# MCU.net
KiCad netlist of a schematic drawn in Altium Designer
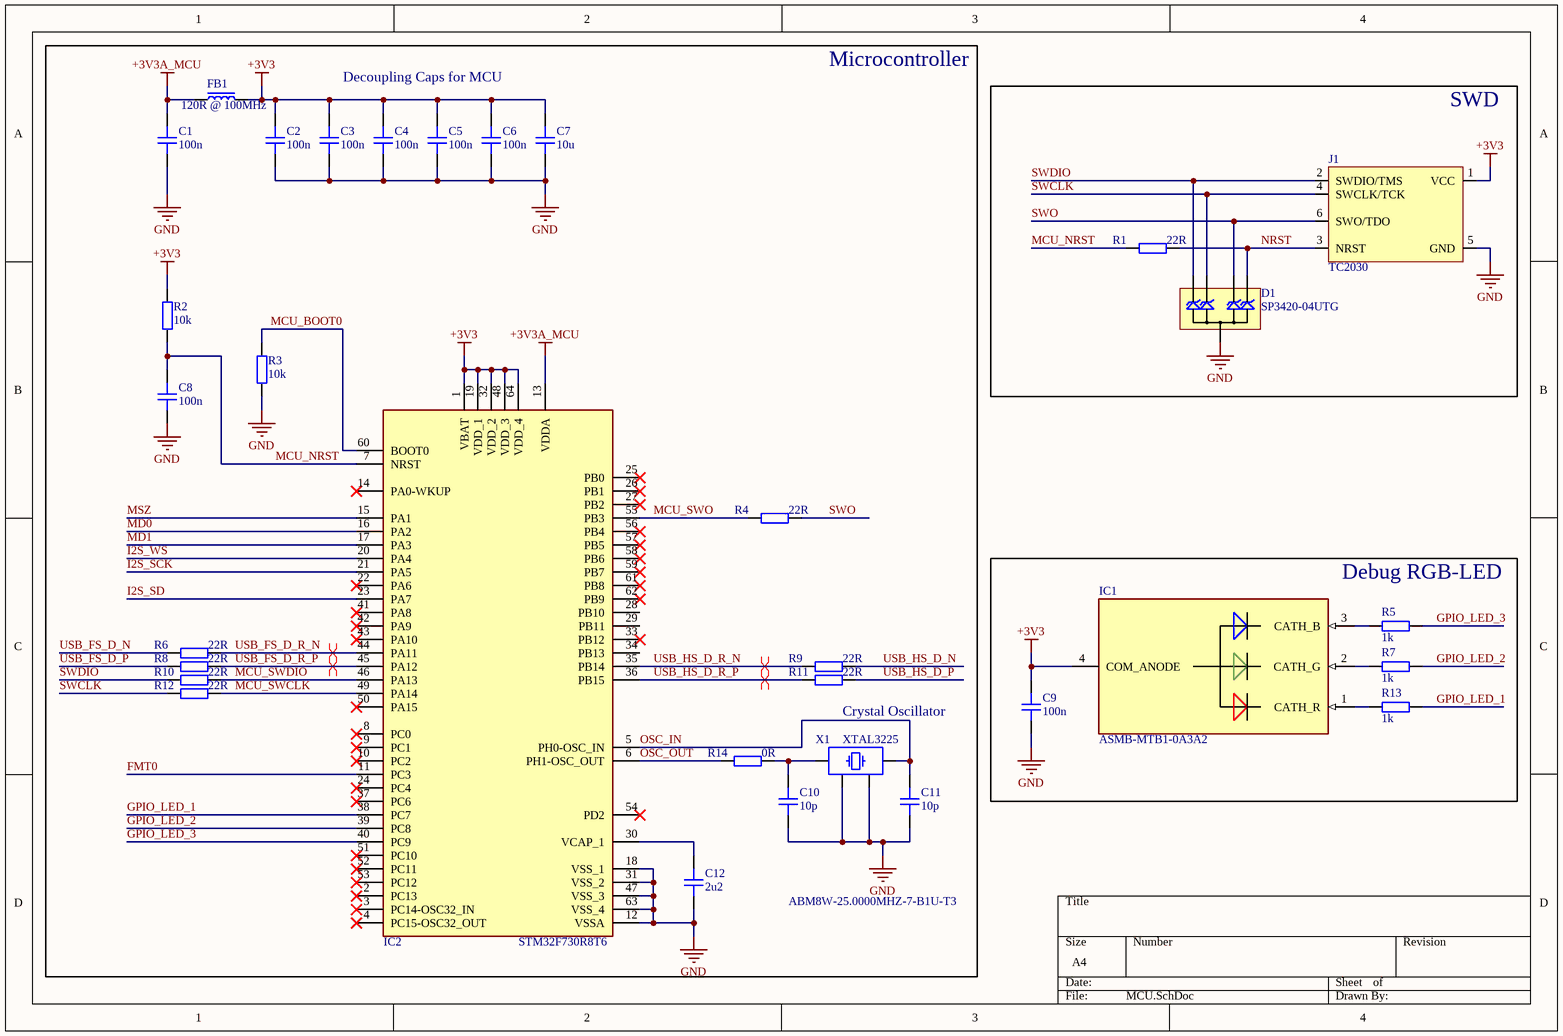
[diagram p0: MCU.SchDoc]

(export (version "E")
  (design (tool "Eeschema 10.0.6"))
  (components
    (comp (ref "C1")
      (value "100n")
      (footprint "CAP_0402")
      (description "Capacitor SMD 0402")
      (libsource (lib "Schematic-Lib-PhilsLab") (part "CAP_0402"))
    )
    (comp (ref "C2")
      (value "100n")
      (footprint "CAP_0402")
      (description "Capacitor SMD 0402")
      (libsource (lib "Schematic-Lib-PhilsLab") (part "CAP_0402"))
    )
    (comp (ref "C3")
      (value "100n")
      (footprint "CAP_0402")
      (description "Capacitor SMD 0402")
      (libsource (lib "Schematic-Lib-PhilsLab") (part "CAP_0402"))
    )
    (comp (ref "C4")
      (value "100n")
      (footprint "CAP_0402")
      (description "Capacitor SMD 0402")
      (libsource (lib "Schematic-Lib-PhilsLab") (part "CAP_0402"))
    )
    (comp (ref "C5")
      (value "100n")
      (footprint "CAP_0402")
      (description "Capacitor SMD 0402")
      (libsource (lib "Schematic-Lib-PhilsLab") (part "CAP_0402"))
    )
    (comp (ref "C6")
      (value "100n")
      (footprint "CAP_0402")
      (description "Capacitor SMD 0402")
      (libsource (lib "Schematic-Lib-PhilsLab") (part "CAP_0402"))
    )
    (comp (ref "C7")
      (value "10u")
      (footprint "CAP_0603")
      (description "Capacitor SMD 0603")
      (libsource (lib "Schematic-Lib-PhilsLab") (part "CAP_0603"))
    )
    (comp (ref "C8")
      (value "100n")
      (footprint "CAP_0402")
      (description "Capacitor SMD 0402")
      (libsource (lib "Schematic-Lib-PhilsLab") (part "CAP_0402"))
    )
    (comp (ref "C9")
      (value "100n")
      (footprint "CAP_0402")
      (description "Capacitor SMD 0402")
      (libsource (lib "Schematic-Lib-PhilsLab") (part "CAP_0402"))
    )
    (comp (ref "C10")
      (value "10p")
      (footprint "CAP_0402")
      (description "Capacitor SMD 0402")
      (libsource (lib "Schematic-Lib-PhilsLab") (part "CAP_0402"))
    )
    (comp (ref "C11")
      (value "10p")
      (footprint "CAP_0402")
      (description "Capacitor SMD 0402")
      (libsource (lib "Schematic-Lib-PhilsLab") (part "CAP_0402"))
    )
    (comp (ref "C12")
      (value "2u2")
      (footprint "CAP_0402")
      (description "Capacitor SMD 0402")
      (libsource (lib "Schematic-Lib-PhilsLab") (part "CAP_0402"))
    )
    (comp (ref "D1")
      (value "SP3420-04UTG")
      (footprint "uDFN-10")
      (description "TVS Diode Array Low Capacitance ESD Protection 4-Channel (Vwork=3V3, Vclamp=6V)")
      (fields (field (name "MANUFACTURER") "Littelfuse"))
      (libsource (lib "Schematic-Lib-PhilsLab") (part "SP3420-04UTG"))
    )
    (comp (ref "FB1")
      (value "120R @ 100MHz")
      (footprint "FB_0402")
      (description "Ferrite Bead SMD 0402")
      (libsource (lib "Schematic-Lib-PhilsLab") (part "FB_0402"))
    )
    (comp (ref "IC1")
      (value "ASMB-MTB1-0A3A2")
      (footprint "BAT_Detector_PCBLib:AVAGO_PLCC4")
      (description "Integrated Circuit")
      (fields (field (name "MOUSER PART NUMBER") "630-ASMB-MTB1-0A3A2"))
      (libsource (lib "BAT_Detector_SCHLib") (part "ASMB-MTB1-0A3A2"))
    )
    (comp (ref "IC2")
      (value "STM32F730R8T6")
      (footprint "BAT_Detector_PCBLib:QFP50P1200X1200X160-64N")
      (description "Integrated Circuit")
      (fields (field (name "MOUSER PART NUMBER") "511-STM32F730R8T6"))
      (libsource (lib "BAT_Detector_SCHLib") (part "STM32F730R8T6"))
    )
    (comp (ref "J1")
      (value "TC2030")
      (footprint "TC2030-FP")
      (description "Tag-Connect No-Solder SWD Debug Connector DO NOT PLACE")
      (fields (field (name "MANUFACTURER") "Tag-Connect"))
      (libsource (lib "Schematic-Lib-PhilsLab") (part "TC2030"))
    )
    (comp (ref "R1")
      (value "22R")
      (footprint "RES_0402")
      (description "Resistor SMD 0402")
      (libsource (lib "Schematic-Lib-PhilsLab") (part "RES_0402"))
    )
    (comp (ref "R2")
      (value "10k")
      (footprint "RES_0402")
      (description "Resistor SMD 0402")
      (libsource (lib "Schematic-Lib-PhilsLab") (part "RES_0402"))
    )
    (comp (ref "R3")
      (value "10k")
      (footprint "RES_0402")
      (description "Resistor SMD 0402")
      (libsource (lib "Schematic-Lib-PhilsLab") (part "RES_0402"))
    )
    (comp (ref "R4")
      (value "22R")
      (footprint "RES_0402")
      (description "Resistor SMD 0402")
      (libsource (lib "Schematic-Lib-PhilsLab") (part "RES_0402"))
    )
    (comp (ref "R5")
      (value "1k")
      (footprint "RES_0402")
      (description "Resistor SMD 0402")
      (libsource (lib "Schematic-Lib-PhilsLab") (part "RES_0402"))
    )
    (comp (ref "R6")
      (value "22R")
      (footprint "RES_0402")
      (description "Resistor SMD 0402")
      (libsource (lib "Schematic-Lib-PhilsLab") (part "RES_0402"))
    )
    (comp (ref "R7")
      (value "1k")
      (footprint "RES_0402")
      (description "Resistor SMD 0402")
      (libsource (lib "Schematic-Lib-PhilsLab") (part "RES_0402"))
    )
    (comp (ref "R8")
      (value "22R")
      (footprint "RES_0402")
      (description "Resistor SMD 0402")
      (libsource (lib "Schematic-Lib-PhilsLab") (part "RES_0402"))
    )
    (comp (ref "R9")
      (value "22R")
      (footprint "RES_0402")
      (description "Resistor SMD 0402")
      (libsource (lib "Schematic-Lib-PhilsLab") (part "RES_0402"))
    )
    (comp (ref "R10")
      (value "22R")
      (footprint "RES_0402")
      (description "Resistor SMD 0402")
      (libsource (lib "Schematic-Lib-PhilsLab") (part "RES_0402"))
    )
    (comp (ref "R11")
      (value "22R")
      (footprint "RES_0402")
      (description "Resistor SMD 0402")
      (libsource (lib "Schematic-Lib-PhilsLab") (part "RES_0402"))
    )
    (comp (ref "R12")
      (value "22R")
      (footprint "RES_0402")
      (description "Resistor SMD 0402")
      (libsource (lib "Schematic-Lib-PhilsLab") (part "RES_0402"))
    )
    (comp (ref "R13")
      (value "1k")
      (footprint "RES_0402")
      (description "Resistor SMD 0402")
      (libsource (lib "Schematic-Lib-PhilsLab") (part "RES_0402"))
    )
    (comp (ref "R14")
      (value "0R")
      (footprint "RES_0402")
      (description "Resistor SMD 0402")
      (libsource (lib "Schematic-Lib-PhilsLab") (part "RES_0402"))
    )
    (comp (ref "X1")
      (value "XTAL3225")
      (footprint "XTAL_3225")
      (description "Crystal SMD 3225")
      (libsource (lib "Schematic-Lib-PhilsLab") (part "XTAL_3225"))
    )
  )
  (nets
    (net (code "1") (name "+3V3") (class "Default")
      (node (ref "C2") (pin "2") (pinfunction "2_2") (pintype "passive"))
      (node (ref "C3") (pin "2") (pinfunction "2_2") (pintype "passive"))
      (node (ref "C4") (pin "2") (pinfunction "2_2") (pintype "passive"))
      (node (ref "C5") (pin "2") (pinfunction "2_2") (pintype "passive"))
      (node (ref "C6") (pin "2") (pinfunction "2_2") (pintype "passive"))
      (node (ref "C7") (pin "2") (pinfunction "2_2") (pintype "passive"))
      (node (ref "C9") (pin "2") (pinfunction "2_2") (pintype "passive"))
      (node (ref "FB1") (pin "2") (pinfunction "2_2") (pintype "passive"))
      (node (ref "IC1") (pin "4") (pinfunction "COM_ANODE_4") (pintype "power_in"))
      (node (ref "IC2") (pin "1") (pinfunction "VBAT_1") (pintype "passive"))
      (node (ref "IC2") (pin "19") (pinfunction "VDD_1_19") (pintype "passive"))
      (node (ref "IC2") (pin "32") (pinfunction "VDD_2_32") (pintype "passive"))
      (node (ref "IC2") (pin "48") (pinfunction "VDD_3_48") (pintype "passive"))
      (node (ref "IC2") (pin "64") (pinfunction "VDD_4_64") (pintype "passive"))
      (node (ref "J1") (pin "1") (pinfunction "VCC_1") (pintype "passive"))
      (node (ref "R2") (pin "1") (pinfunction "1_1") (pintype "passive"))
    )
    (net (code "2") (name "+3V3A_MCU") (class "Default")
      (node (ref "C1") (pin "2") (pinfunction "2_2") (pintype "passive"))
      (node (ref "FB1") (pin "1") (pinfunction "1_1") (pintype "passive"))
      (node (ref "IC2") (pin "13") (pinfunction "VDDA_13") (pintype "passive"))
    )
    (net (code "3") (name "/FMT0") (class "Default")
      (node (ref "IC2") (pin "11") (pinfunction "PC3_11") (pintype "passive"))
    )
    (net (code "4") (name "/GPIO_LED_1") (class "Default")
      (node (ref "IC2") (pin "38") (pinfunction "PC7_38") (pintype "passive"))
      (node (ref "R13") (pin "1") (pinfunction "1_1") (pintype "passive"))
    )
    (net (code "5") (name "/GPIO_LED_2") (class "Default")
      (node (ref "IC2") (pin "39") (pinfunction "PC8_39") (pintype "passive"))
      (node (ref "R7") (pin "1") (pinfunction "1_1") (pintype "passive"))
    )
    (net (code "6") (name "/GPIO_LED_3") (class "Default")
      (node (ref "IC2") (pin "40") (pinfunction "PC9_40") (pintype "passive"))
      (node (ref "R5") (pin "1") (pinfunction "1_1") (pintype "passive"))
    )
    (net (code "7") (name "/I2S_SCK") (class "Default")
      (node (ref "IC2") (pin "21") (pinfunction "PA5_21") (pintype "passive"))
    )
    (net (code "8") (name "/I2S_SD") (class "Default")
      (node (ref "IC2") (pin "23") (pinfunction "PA7_23") (pintype "passive"))
    )
    (net (code "9") (name "/I2S_WS") (class "Default")
      (node (ref "IC2") (pin "20") (pinfunction "PA4_20") (pintype "passive"))
    )
    (net (code "10") (name "/MCU_BOOT0") (class "Default")
      (node (ref "IC2") (pin "60") (pinfunction "BOOT0_60") (pintype "passive"))
      (node (ref "R3") (pin "2") (pinfunction "2_2") (pintype "passive"))
    )
    (net (code "11") (name "/MCU_NRST") (class "Default")
      (node (ref "C8") (pin "2") (pinfunction "2_2") (pintype "passive"))
      (node (ref "IC2") (pin "7") (pinfunction "NRST_7") (pintype "passive"))
      (node (ref "R1") (pin "1") (pinfunction "1_1") (pintype "passive"))
      (node (ref "R2") (pin "2") (pinfunction "2_2") (pintype "passive"))
    )
    (net (code "12") (name "/MCU_SWCLK") (class "Default")
      (node (ref "IC2") (pin "49") (pinfunction "PA14_49") (pintype "passive"))
      (node (ref "R12") (pin "2") (pinfunction "2_2") (pintype "passive"))
    )
    (net (code "13") (name "/MCU_SWDIO") (class "Default")
      (node (ref "IC2") (pin "46") (pinfunction "PA13_46") (pintype "passive"))
      (node (ref "R10") (pin "2") (pinfunction "2_2") (pintype "passive"))
    )
    (net (code "14") (name "/MCU_SWO") (class "Default")
      (node (ref "IC2") (pin "55") (pinfunction "PB3_55") (pintype "passive"))
      (node (ref "R4") (pin "1") (pinfunction "1_1") (pintype "passive"))
    )
    (net (code "15") (name "/MD0") (class "Default")
      (node (ref "IC2") (pin "16") (pinfunction "PA2_16") (pintype "passive"))
    )
    (net (code "16") (name "/MD1") (class "Default")
      (node (ref "IC2") (pin "17") (pinfunction "PA3_17") (pintype "passive"))
    )
    (net (code "17") (name "/MSZ") (class "Default")
      (node (ref "IC2") (pin "15") (pinfunction "PA1_15") (pintype "passive"))
    )
    (net (code "18") (name "/NRST") (class "Default")
      (node (ref "D1") (pin "56") (pintype "passive"))
      (node (ref "J1") (pin "3") (pinfunction "NRST_3") (pintype "passive"))
      (node (ref "R1") (pin "2") (pinfunction "2_2") (pintype "passive"))
    )
    (net (code "19") (name "/OSC_IN") (class "Default")
      (node (ref "C11") (pin "2") (pinfunction "2_2") (pintype "passive"))
      (node (ref "IC2") (pin "5") (pinfunction "PH0-OSC_IN_5") (pintype "passive"))
      (node (ref "X1") (pin "1") (pinfunction "1_1") (pintype "passive"))
    )
    (net (code "20") (name "/OSC_OUT") (class "Default")
      (node (ref "IC2") (pin "6") (pinfunction "PH1-OSC_OUT_6") (pintype "passive"))
      (node (ref "R14") (pin "1") (pinfunction "1_1") (pintype "passive"))
    )
    (net (code "21") (name "/SWCLK") (class "Default")
      (node (ref "D1") (pin "29") (pintype "passive"))
      (node (ref "J1") (pin "4") (pinfunction "SWCLK/TCK_4") (pintype "passive"))
      (node (ref "R12") (pin "1") (pinfunction "1_1") (pintype "passive"))
    )
    (net (code "22") (name "/SWDIO") (class "Default")
      (node (ref "D1") (pin "110") (pintype "passive"))
      (node (ref "J1") (pin "2") (pinfunction "SWDIO/TMS_2") (pintype "passive"))
      (node (ref "R10") (pin "1") (pinfunction "1_1") (pintype "passive"))
    )
    (net (code "23") (name "/SWO") (class "Default")
      (node (ref "D1") (pin "47") (pintype "passive"))
      (node (ref "J1") (pin "6") (pinfunction "SWO/TDO_6") (pintype "passive"))
      (node (ref "R4") (pin "2") (pinfunction "2_2") (pintype "passive"))
    )
    (net (code "24") (name "/USB_FS_D_N") (class "Default")
      (node (ref "R6") (pin "1") (pinfunction "1_1") (pintype "passive"))
    )
    (net (code "25") (name "/USB_FS_D_P") (class "Default")
      (node (ref "R8") (pin "1") (pinfunction "1_1") (pintype "passive"))
    )
    (net (code "26") (name "/USB_FS_D_R_N") (class "Default")
      (node (ref "IC2") (pin "44") (pinfunction "PA11_44") (pintype "passive"))
      (node (ref "R6") (pin "2") (pinfunction "2_2") (pintype "passive"))
    )
    (net (code "27") (name "/USB_FS_D_R_P") (class "Default")
      (node (ref "IC2") (pin "45") (pinfunction "PA12_45") (pintype "passive"))
      (node (ref "R8") (pin "2") (pinfunction "2_2") (pintype "passive"))
    )
    (net (code "28") (name "/USB_HS_D_N") (class "Default")
      (node (ref "R9") (pin "2") (pinfunction "2_2") (pintype "passive"))
    )
    (net (code "29") (name "/USB_HS_D_P") (class "Default")
      (node (ref "R11") (pin "2") (pinfunction "2_2") (pintype "passive"))
    )
    (net (code "30") (name "/USB_HS_D_R_N") (class "Default")
      (node (ref "IC2") (pin "35") (pinfunction "PB14_35") (pintype "passive"))
      (node (ref "R9") (pin "1") (pinfunction "1_1") (pintype "passive"))
    )
    (net (code "31") (name "/USB_HS_D_R_P") (class "Default")
      (node (ref "IC2") (pin "36") (pinfunction "PB15_36") (pintype "passive"))
      (node (ref "R11") (pin "1") (pinfunction "1_1") (pintype "passive"))
    )
    (net (code "32") (name "GND") (class "Default")
      (node (ref "C1") (pin "1") (pinfunction "1_1") (pintype "passive"))
      (node (ref "C10") (pin "1") (pinfunction "1_1") (pintype "passive"))
      (node (ref "C11") (pin "1") (pinfunction "1_1") (pintype "passive"))
      (node (ref "C12") (pin "1") (pinfunction "1_1") (pintype "passive"))
      (node (ref "C2") (pin "1") (pinfunction "1_1") (pintype "passive"))
      (node (ref "C3") (pin "1") (pinfunction "1_1") (pintype "passive"))
      (node (ref "C4") (pin "1") (pinfunction "1_1") (pintype "passive"))
      (node (ref "C5") (pin "1") (pinfunction "1_1") (pintype "passive"))
      (node (ref "C6") (pin "1") (pinfunction "1_1") (pintype "passive"))
      (node (ref "C7") (pin "1") (pinfunction "1_1") (pintype "passive"))
      (node (ref "C8") (pin "1") (pinfunction "1_1") (pintype "passive"))
      (node (ref "C9") (pin "1") (pinfunction "1_1") (pintype "passive"))
      (node (ref "D1") (pin "38") (pinfunction "GND_38") (pintype "passive"))
      (node (ref "IC2") (pin "12") (pinfunction "VSSA_12") (pintype "passive"))
      (node (ref "IC2") (pin "18") (pinfunction "VSS_1_18") (pintype "passive"))
      (node (ref "IC2") (pin "31") (pinfunction "VSS_2_31") (pintype "passive"))
      (node (ref "IC2") (pin "47") (pinfunction "VSS_3_47") (pintype "passive"))
      (node (ref "IC2") (pin "63") (pinfunction "VSS_4_63") (pintype "passive"))
      (node (ref "J1") (pin "5") (pinfunction "GND_5") (pintype "passive"))
      (node (ref "R3") (pin "1") (pinfunction "1_1") (pintype "passive"))
      (node (ref "X1") (pin "2") (pinfunction "2_2") (pintype "passive"))
      (node (ref "X1") (pin "4") (pinfunction "4_4") (pintype "passive"))
    )
    (net (code "33") (name "Net-(C10-Pad2)") (class "Default")
      (node (ref "C10") (pin "2") (pinfunction "2_2") (pintype "passive"))
      (node (ref "R14") (pin "2") (pinfunction "2_2") (pintype "passive"))
      (node (ref "X1") (pin "3") (pinfunction "3_3") (pintype "passive"))
    )
    (net (code "34") (name "Net-(IC1-CATH_B)") (class "Default")
      (node (ref "IC1") (pin "3") (pinfunction "CATH_B_3") (pintype "input"))
      (node (ref "R5") (pin "2") (pinfunction "2_2") (pintype "passive"))
    )
    (net (code "35") (name "Net-(IC1-CATH_G)") (class "Default")
      (node (ref "IC1") (pin "2") (pinfunction "CATH_G_2") (pintype "input"))
      (node (ref "R7") (pin "2") (pinfunction "2_2") (pintype "passive"))
    )
    (net (code "36") (name "Net-(IC1-CATH_R)") (class "Default")
      (node (ref "IC1") (pin "1") (pinfunction "CATH_R_1") (pintype "input"))
      (node (ref "R13") (pin "2") (pinfunction "2_2") (pintype "passive"))
    )
    (net (code "37") (name "Net-(IC2-VCAP_1)") (class "Default")
      (node (ref "C12") (pin "2") (pinfunction "2_2") (pintype "passive"))
      (node (ref "IC2") (pin "30") (pinfunction "VCAP_1_30") (pintype "passive"))
    )
    (net (code "38") (name "unconnected-(IC2-PA0-WKUP-Pad14)") (class "Default")
      (node (ref "IC2") (pin "14") (pinfunction "PA0-WKUP_14") (pintype "passive+no_connect"))
    )
    (net (code "39") (name "unconnected-(IC2-PA6-Pad22)") (class "Default")
      (node (ref "IC2") (pin "22") (pinfunction "PA6_22") (pintype "passive+no_connect"))
    )
    (net (code "40") (name "unconnected-(IC2-PA8-Pad41)") (class "Default")
      (node (ref "IC2") (pin "41") (pinfunction "PA8_41") (pintype "passive+no_connect"))
    )
    (net (code "41") (name "unconnected-(IC2-PA9-Pad42)") (class "Default")
      (node (ref "IC2") (pin "42") (pinfunction "PA9_42") (pintype "passive+no_connect"))
    )
    (net (code "42") (name "unconnected-(IC2-PA10-Pad43)") (class "Default")
      (node (ref "IC2") (pin "43") (pinfunction "PA10_43") (pintype "passive+no_connect"))
    )
    (net (code "43") (name "unconnected-(IC2-PA15-Pad50)") (class "Default")
      (node (ref "IC2") (pin "50") (pinfunction "PA15_50") (pintype "passive+no_connect"))
    )
    (net (code "44") (name "unconnected-(IC2-PB0-Pad25)") (class "Default")
      (node (ref "IC2") (pin "25") (pinfunction "PB0_25") (pintype "passive+no_connect"))
    )
    (net (code "45") (name "unconnected-(IC2-PB1-Pad26)") (class "Default")
      (node (ref "IC2") (pin "26") (pinfunction "PB1_26") (pintype "passive+no_connect"))
    )
    (net (code "46") (name "unconnected-(IC2-PB2-Pad27)") (class "Default")
      (node (ref "IC2") (pin "27") (pinfunction "PB2_27") (pintype "passive+no_connect"))
    )
    (net (code "47") (name "unconnected-(IC2-PB4-Pad56)") (class "Default")
      (node (ref "IC2") (pin "56") (pinfunction "PB4_56") (pintype "passive+no_connect"))
    )
    (net (code "48") (name "unconnected-(IC2-PB5-Pad57)") (class "Default")
      (node (ref "IC2") (pin "57") (pinfunction "PB5_57") (pintype "passive+no_connect"))
    )
    (net (code "49") (name "unconnected-(IC2-PB6-Pad58)") (class "Default")
      (node (ref "IC2") (pin "58") (pinfunction "PB6_58") (pintype "passive+no_connect"))
    )
    (net (code "50") (name "unconnected-(IC2-PB7-Pad59)") (class "Default")
      (node (ref "IC2") (pin "59") (pinfunction "PB7_59") (pintype "passive+no_connect"))
    )
    (net (code "51") (name "unconnected-(IC2-PB8-Pad61)") (class "Default")
      (node (ref "IC2") (pin "61") (pinfunction "PB8_61") (pintype "passive+no_connect"))
    )
    (net (code "52") (name "unconnected-(IC2-PB9-Pad62)") (class "Default")
      (node (ref "IC2") (pin "62") (pinfunction "PB9_62") (pintype "passive+no_connect"))
    )
    (net (code "53") (name "unconnected-(IC2-PB10-Pad28)") (class "Default")
      (node (ref "IC2") (pin "28") (pinfunction "PB10_28") (pintype "passive"))
    )
    (net (code "54") (name "unconnected-(IC2-PB11-Pad29)") (class "Default")
      (node (ref "IC2") (pin "29") (pinfunction "PB11_29") (pintype "passive"))
    )
    (net (code "55") (name "unconnected-(IC2-PB12-Pad33)") (class "Default")
      (node (ref "IC2") (pin "33") (pinfunction "PB12_33") (pintype "passive+no_connect"))
    )
    (net (code "56") (name "unconnected-(IC2-PB13-Pad34)") (class "Default")
      (node (ref "IC2") (pin "34") (pinfunction "PB13_34") (pintype "passive"))
    )
    (net (code "57") (name "unconnected-(IC2-PC0-Pad8)") (class "Default")
      (node (ref "IC2") (pin "8") (pinfunction "PC0_8") (pintype "passive+no_connect"))
    )
    (net (code "58") (name "unconnected-(IC2-PC1-Pad9)") (class "Default")
      (node (ref "IC2") (pin "9") (pinfunction "PC1_9") (pintype "passive+no_connect"))
    )
    (net (code "59") (name "unconnected-(IC2-PC2-Pad10)") (class "Default")
      (node (ref "IC2") (pin "10") (pinfunction "PC2_10") (pintype "passive+no_connect"))
    )
    (net (code "60") (name "unconnected-(IC2-PC4-Pad24)") (class "Default")
      (node (ref "IC2") (pin "24") (pinfunction "PC4_24") (pintype "passive+no_connect"))
    )
    (net (code "61") (name "unconnected-(IC2-PC6-Pad37)") (class "Default")
      (node (ref "IC2") (pin "37") (pinfunction "PC6_37") (pintype "passive+no_connect"))
    )
    (net (code "62") (name "unconnected-(IC2-PC10-Pad51)") (class "Default")
      (node (ref "IC2") (pin "51") (pinfunction "PC10_51") (pintype "passive+no_connect"))
    )
    (net (code "63") (name "unconnected-(IC2-PC11-Pad52)") (class "Default")
      (node (ref "IC2") (pin "52") (pinfunction "PC11_52") (pintype "passive+no_connect"))
    )
    (net (code "64") (name "unconnected-(IC2-PC12-Pad53)") (class "Default")
      (node (ref "IC2") (pin "53") (pinfunction "PC12_53") (pintype "passive+no_connect"))
    )
    (net (code "65") (name "unconnected-(IC2-PC13-Pad2)") (class "Default")
      (node (ref "IC2") (pin "2") (pinfunction "PC13_2") (pintype "passive+no_connect"))
    )
    (net (code "66") (name "unconnected-(IC2-PC14-OSC32_IN-Pad3)") (class "Default")
      (node (ref "IC2") (pin "3") (pinfunction "PC14-OSC32_IN_3") (pintype "passive+no_connect"))
    )
    (net (code "67") (name "unconnected-(IC2-PC15-OSC32_OUT-Pad4)") (class "Default")
      (node (ref "IC2") (pin "4") (pinfunction "PC15-OSC32_OUT_4") (pintype "passive+no_connect"))
    )
    (net (code "68") (name "unconnected-(IC2-PD2-Pad54)") (class "Default")
      (node (ref "IC2") (pin "54") (pinfunction "PD2_54") (pintype "passive+no_connect"))
    )
  )
)
